# UC3844_-_SIMU_COMPACTA.net
KiCad netlist of a schematic drawn in Altium Designer
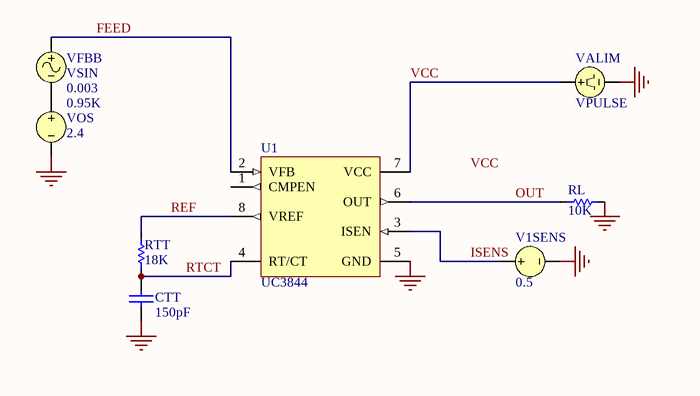
[diagram p0: UC3844 - SIMU COMPACTA.SCHDOC]

(export (version "E")
  (design (tool "Eeschema 10.0.6"))
  (components
    (comp (ref "CTT")
      (value "150pF")
      (footprint "0805")
      (description "Capacitor")
      (fields (field (name "VOLTAGE") "50V") (field (name "Comment") "Cap"))
      (libsource (lib "FEDE") (part "Cap"))
    )
    (comp (ref "RL")
      (value "10K")
      (footprint "0805")
      (description "Resistor")
      (fields (field (name "POWER") "0.25W") (field (name "Comment") "Res"))
      (libsource (lib "FEDE") (part "Res"))
    )
    (comp (ref "RTT")
      (value "18K")
      (footprint "0805")
      (description "Resistor")
      (fields (field (name "POWER") "0.25W") (field (name "Comment") "Res"))
      (libsource (lib "FEDE") (part "Res"))
    )
    (comp (ref "U1")
      (value "UC3844")
      (footprint "DIP8Z")
      (description "Current-Mode PWM Controller")
      (libsource (lib "FEDE") (part "UC3844"))
    )
    (comp (ref "V1SENS")
      (value "0.5")
      (description "Voltage Source")
      (fields (field (name "Comment") "VSRC") (field (name "PUBLISHER") "Altium Limited"))
      (libsource (lib "Simulation Sources") (part "VSRC"))
    )
    (comp (ref "VALIM")
      (value "VPULSE")
      (description "Pulse Voltage Source")
      (fields (field (name "PUBLISHER") "Altium Limited"))
      (libsource (lib "Simulation Sources") (part "VPULSE"))
    )
    (comp (ref "VFBB")
      (value "VSIN")
      (description "Sinusoidal Voltage Source")
      (fields
        (field (name "AMPLITUDE") "0.003")
        (field (name "FREQUENCY") "0.95K")
        (field (name "PUBLISHER") "Altium Limited")
      )
      (libsource (lib "Simulation Sources") (part "VSIN"))
    )
    (comp (ref "VOS")
      (value "2.4")
      (description "Voltage Source")
      (fields (field (name "Comment") "VSRC") (field (name "PUBLISHER") "Altium Limited"))
      (libsource (lib "Simulation Sources") (part "VSRC"))
    )
  )
  (nets
    (net (code "1") (name "/FEED") (class "Default")
      (node (ref "U1") (pin "2") (pinfunction "VFB_2") (pintype "input"))
      (node (ref "VFBB") (pin "1") (pinfunction "1_1") (pintype "passive"))
    )
    (net (code "2") (name "/ISENS") (class "Default")
      (node (ref "U1") (pin "3") (pinfunction "ISEN_3") (pintype "input"))
      (node (ref "V1SENS") (pin "1") (pinfunction "1_1") (pintype "passive"))
    )
    (net (code "3") (name "/OUT") (class "Default")
      (node (ref "RL") (pin "2") (pinfunction "2_2") (pintype "passive"))
      (node (ref "U1") (pin "6") (pinfunction "OUT_6") (pintype "output"))
    )
    (net (code "4") (name "/REF") (class "Default")
      (node (ref "RTT") (pin "2") (pinfunction "2_2") (pintype "passive"))
      (node (ref "U1") (pin "8") (pinfunction "VREF_8") (pintype "output"))
    )
    (net (code "5") (name "/RTCT") (class "Default")
      (node (ref "CTT") (pin "2") (pinfunction "2_2") (pintype "passive"))
      (node (ref "RTT") (pin "1") (pinfunction "1_1") (pintype "passive"))
      (node (ref "U1") (pin "4") (pinfunction "RT/CT_4") (pintype "passive"))
    )
    (net (code "6") (name "/VCC") (class "Default")
      (node (ref "U1") (pin "7") (pinfunction "VCC_7") (pintype "power_in"))
      (node (ref "VALIM") (pin "1") (pinfunction "1_1") (pintype "passive"))
    )
    (net (code "7") (name "GND") (class "Default")
      (node (ref "CTT") (pin "1") (pinfunction "1_1") (pintype "passive"))
      (node (ref "RL") (pin "1") (pinfunction "1_1") (pintype "passive"))
      (node (ref "U1") (pin "5") (pinfunction "GND_5") (pintype "power_in"))
      (node (ref "V1SENS") (pin "2") (pinfunction "2_2") (pintype "passive"))
      (node (ref "VALIM") (pin "2") (pinfunction "2_2") (pintype "passive"))
      (node (ref "VOS") (pin "2") (pinfunction "2_2") (pintype "passive"))
    )
    (net (code "8") (name "Net-(VFBB-Pad2)") (class "Default")
      (node (ref "VFBB") (pin "2") (pinfunction "2_2") (pintype "passive"))
      (node (ref "VOS") (pin "1") (pinfunction "1_1") (pintype "passive"))
    )
    (net (code "9") (name "unconnected-(U1-CMPEN-Pad1)") (class "Default")
      (node (ref "U1") (pin "1") (pinfunction "CMPEN_1") (pintype "output"))
    )
  )
)
